# Photodiode.net
KiCad netlist of a schematic drawn in Altium Designer
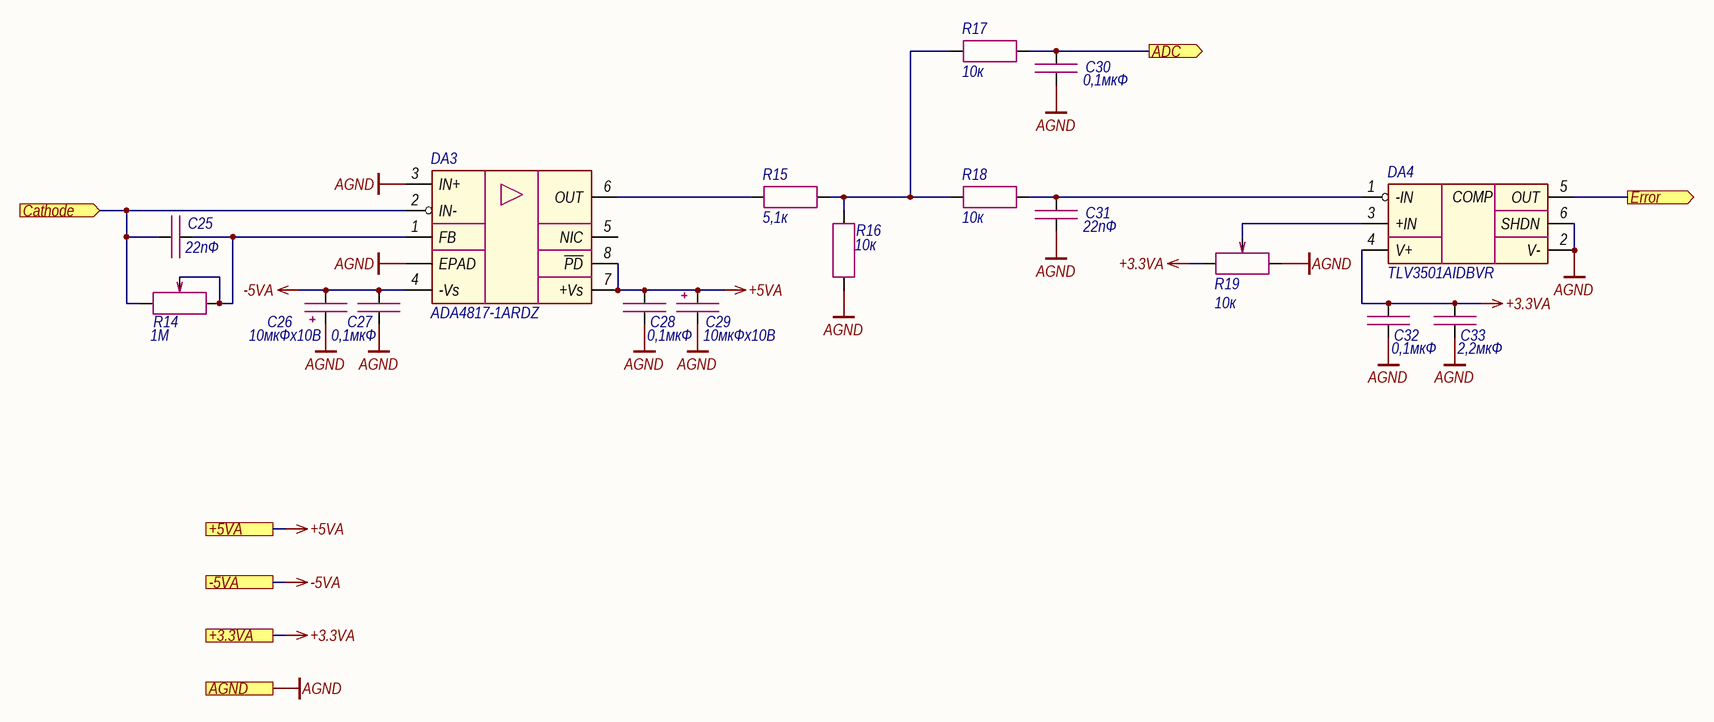
[diagram p0: Photodiode.SchDoc]

(export (version "E")
  (design (tool "Eeschema 10.0.6"))
  (components
    (comp (ref "C25")
      (value "22пФ")
      (footprint "Pcb_library:CAP_0603")
      (fields (field (name "MANUFACTURER") "Murata"))
      (libsource (lib "Schem_library") (part "Capacitor"))
    )
    (comp (ref "C26")
      (value "10мкФх10B")
      (footprint "Pcb_library:CAP_A")
      (libsource (lib "Schem_library") (part "Capacitor_Polar"))
    )
    (comp (ref "C27")
      (value "0,1мкФ")
      (footprint "Pcb_library:CAP_0603")
      (fields (field (name "MANUFACTURER") "Murata"))
      (libsource (lib "Schem_library") (part "Capacitor"))
    )
    (comp (ref "C28")
      (value "0,1мкФ")
      (footprint "Pcb_library:CAP_0603")
      (fields (field (name "MANUFACTURER") "Murata"))
      (libsource (lib "Schem_library") (part "Capacitor"))
    )
    (comp (ref "C29")
      (value "10мкФх10B")
      (footprint "Pcb_library:CAP_A")
      (libsource (lib "Schem_library") (part "Capacitor_Polar"))
    )
    (comp (ref "C30")
      (value "0,1мкФ")
      (footprint "Pcb_library:CAP_0603")
      (fields (field (name "MANUFACTURER") "Murata"))
      (libsource (lib "Schem_library") (part "Capacitor"))
    )
    (comp (ref "C31")
      (value "22пФ")
      (footprint "Pcb_library:CAP_0603")
      (fields (field (name "MANUFACTURER") "Murata"))
      (libsource (lib "Schem_library") (part "Capacitor"))
    )
    (comp (ref "C32")
      (value "0,1мкФ")
      (footprint "Pcb_library:CAP_0603")
      (fields (field (name "MANUFACTURER") "Murata"))
      (libsource (lib "Schem_library") (part "Capacitor"))
    )
    (comp (ref "C33")
      (value "2,2мкФ")
      (footprint "Pcb_library:CAP_0603")
      (fields (field (name "MANUFACTURER") "Murata"))
      (libsource (lib "Schem_library") (part "Capacitor"))
    )
    (comp (ref "DA3")
      (value "ADA4817-1ARDZ")
      (footprint "Pcb_library:SOIC-8 EPAD")
      (fields (field (name "MANUFACTURER") "Analog Devices"))
      (libsource (lib "Schem_library") (part "ADA4817-1ARDZ"))
    )
    (comp (ref "DA4")
      (value "TLV3501AIDBVR")
      (footprint "Pcb_library:SOT-23-6")
      (fields (field (name "MANUFACTURER") "Texas Instruments"))
      (libsource (lib "Schem_library") (part "TLV3501"))
    )
    (comp (ref "R14")
      (value "1М")
      (footprint "Pcb_library:3224W")
      (fields (field (name "MANUFACTURER") "Bourns"))
      (libsource (lib "Schem_library") (part "Resistor_Variable"))
    )
    (comp (ref "R15")
      (value "5,1к")
      (footprint "Pcb_library:RES_0603")
      (fields (field (name "MANUFACTURER") "Yageo"))
      (libsource (lib "Schem_library") (part "Resistor"))
    )
    (comp (ref "R16")
      (value "10к")
      (footprint "Pcb_library:RES_0603")
      (fields (field (name "MANUFACTURER") "Yageo"))
      (libsource (lib "Schem_library") (part "Resistor"))
    )
    (comp (ref "R17")
      (value "10к")
      (footprint "Pcb_library:RES_0603")
      (fields (field (name "MANUFACTURER") "Yageo"))
      (libsource (lib "Schem_library") (part "Resistor"))
    )
    (comp (ref "R18")
      (value "10к")
      (footprint "Pcb_library:RES_0603")
      (fields (field (name "MANUFACTURER") "Yageo"))
      (libsource (lib "Schem_library") (part "Resistor"))
    )
    (comp (ref "R19")
      (value "10к")
      (footprint "Pcb_library:3224W")
      (fields (field (name "MANUFACTURER") "Bourns"))
      (libsource (lib "Schem_library") (part "Resistor_Variable"))
    )
  )
  (nets
    (net (code "1") (name "+3.3VA") (class "Default")
      (node (ref "C32") (pin "1") (pinfunction "1_1") (pintype "passive"))
      (node (ref "C33") (pin "1") (pinfunction "1_1") (pintype "passive"))
      (node (ref "DA4") (pin "4") (pinfunction "V+_4") (pintype "passive"))
      (node (ref "R19") (pin "3") (pintype "passive"))
    )
    (net (code "2") (name "+5VA") (class "Default")
      (node (ref "C28") (pin "1") (pinfunction "1_1") (pintype "passive"))
      (node (ref "C29") (pin "1") (pinfunction "1_1") (pintype "passive"))
      (node (ref "DA3") (pin "7") (pinfunction "+Vs_7") (pintype "passive"))
      (node (ref "DA3") (pin "8") (pinfunction "~{PD}_8") (pintype "passive"))
    )
    (net (code "3") (name "-5VA") (class "Default")
      (node (ref "C26") (pin "2") (pinfunction "2_2") (pintype "passive"))
      (node (ref "C27") (pin "1") (pinfunction "1_1") (pintype "passive"))
      (node (ref "DA3") (pin "4") (pinfunction "-Vs_4") (pintype "passive"))
    )
    (net (code "4") (name "/ADC") (class "Default")
      (node (ref "C30") (pin "1") (pinfunction "1_1") (pintype "passive"))
      (node (ref "R17") (pin "2") (pinfunction "2_2") (pintype "passive"))
    )
    (net (code "5") (name "/Cathode") (class "Default")
      (node (ref "C25") (pin "2") (pinfunction "2_2") (pintype "passive"))
      (node (ref "DA3") (pin "2") (pinfunction "IN-_2") (pintype "passive"))
      (node (ref "R14") (pin "1") (pintype "passive"))
    )
    (net (code "6") (name "/Error") (class "Default")
      (node (ref "DA4") (pin "5") (pinfunction "OUT_5") (pintype "passive"))
    )
    (net (code "7") (name "AGND") (class "Default")
      (node (ref "C26") (pin "1") (pinfunction "1_1") (pintype "passive"))
      (node (ref "C27") (pin "2") (pinfunction "2_2") (pintype "passive"))
      (node (ref "C28") (pin "2") (pinfunction "2_2") (pintype "passive"))
      (node (ref "C29") (pin "2") (pinfunction "2_2") (pintype "passive"))
      (node (ref "C30") (pin "2") (pinfunction "2_2") (pintype "passive"))
      (node (ref "C31") (pin "2") (pinfunction "2_2") (pintype "passive"))
      (node (ref "C32") (pin "2") (pinfunction "2_2") (pintype "passive"))
      (node (ref "C33") (pin "2") (pinfunction "2_2") (pintype "passive"))
      (node (ref "DA3") (pin "3") (pinfunction "IN+_3") (pintype "passive"))
      (node (ref "DA3") (pin "EPAD") (pinfunction "EPAD_EPAD") (pintype "passive"))
      (node (ref "DA4") (pin "2") (pinfunction "V-_2") (pintype "passive"))
      (node (ref "DA4") (pin "6") (pinfunction "SHDN_6") (pintype "passive"))
      (node (ref "R16") (pin "2") (pinfunction "2_2") (pintype "passive"))
      (node (ref "R19") (pin "1") (pintype "passive"))
    )
    (net (code "8") (name "Net-(DA3-FB)") (class "Default")
      (node (ref "C25") (pin "1") (pinfunction "1_1") (pintype "passive"))
      (node (ref "DA3") (pin "1") (pinfunction "FB_1") (pintype "passive"))
      (node (ref "R14") (pin "2") (pintype "passive"))
      (node (ref "R14") (pin "3") (pintype "passive"))
    )
    (net (code "9") (name "Net-(DA3-OUT)") (class "Default")
      (node (ref "DA3") (pin "6") (pinfunction "OUT_6") (pintype "passive"))
      (node (ref "R15") (pin "1") (pinfunction "1_1") (pintype "passive"))
    )
    (net (code "10") (name "Net-(DA4-+IN)") (class "Default")
      (node (ref "DA4") (pin "3") (pinfunction "+IN_3") (pintype "passive"))
      (node (ref "R19") (pin "2") (pintype "passive"))
    )
    (net (code "11") (name "Net-(DA4--IN)") (class "Default")
      (node (ref "C31") (pin "1") (pinfunction "1_1") (pintype "passive"))
      (node (ref "DA4") (pin "1") (pinfunction "-IN_1") (pintype "passive"))
      (node (ref "R18") (pin "2") (pinfunction "2_2") (pintype "passive"))
    )
    (net (code "12") (name "Net-(R15-Pad2)") (class "Default")
      (node (ref "R15") (pin "2") (pinfunction "2_2") (pintype "passive"))
      (node (ref "R16") (pin "1") (pinfunction "1_1") (pintype "passive"))
      (node (ref "R17") (pin "1") (pinfunction "1_1") (pintype "passive"))
      (node (ref "R18") (pin "1") (pinfunction "1_1") (pintype "passive"))
    )
    (net (code "13") (name "unconnected-(DA3-NIC-Pad5)") (class "Default")
      (node (ref "DA3") (pin "5") (pinfunction "NIC_5") (pintype "passive"))
    )
  )
)
